# sar20-afbr-s50-adapter.net
KiCad netlist of a schematic drawn in Altium Designer
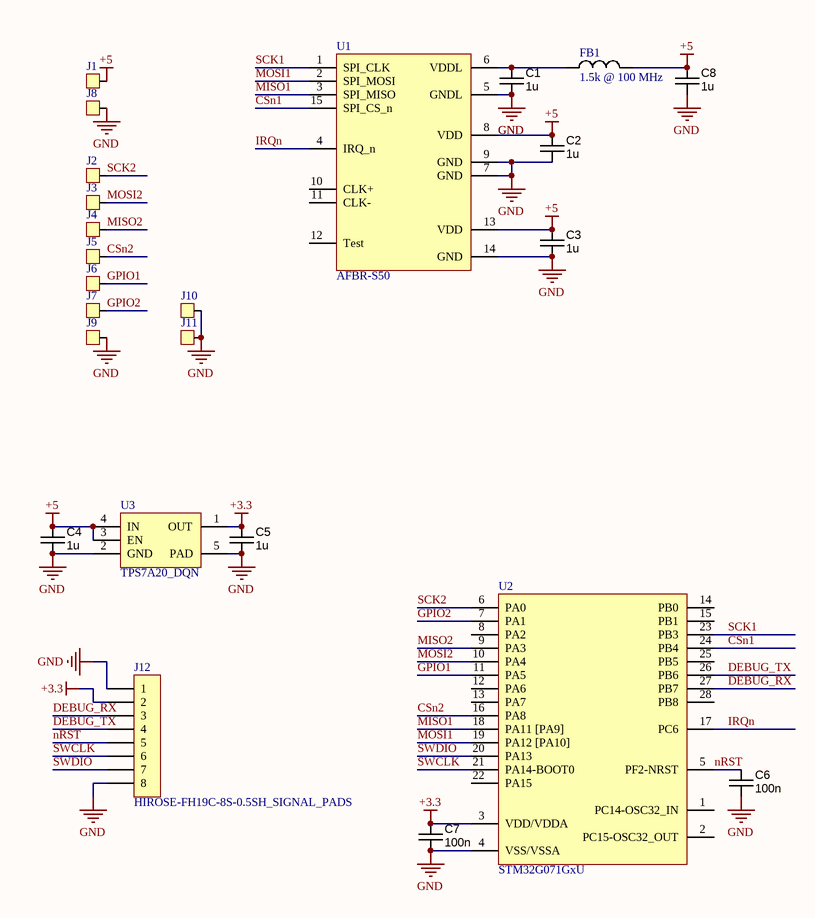
[diagram p0: sar20-afbr-s50-adapter.SchDoc]

(export (version "E")
  (design (tool "Eeschema 10.0.6"))
  (components
    (comp (ref "C1")
      (value "1u")
      (footprint "CAPC1005X55N")
      (description "Capacitor SMD Cer 100nF 10% 16V X5R 0402")
      (fields (field (name "TOLERANCE") "±10%"))
      (libsource (lib "PBL - Capacitors") (part "CAPC_100n_0402_X5R_16V_10%"))
    )
    (comp (ref "C2")
      (value "1u")
      (footprint "CAPC1005X55N")
      (description "Capacitor SMD Cer 100nF 10% 16V X5R 0402")
      (fields (field (name "TOLERANCE") "±10%"))
      (libsource (lib "PBL - Capacitors") (part "CAPC_100n_0402_X5R_16V_10%"))
    )
    (comp (ref "C3")
      (value "1u")
      (footprint "CAPC1005X55N")
      (description "Capacitor SMD Cer 100nF 10% 16V X5R 0402")
      (fields (field (name "TOLERANCE") "±10%"))
      (libsource (lib "PBL - Capacitors") (part "CAPC_100n_0402_X5R_16V_10%"))
    )
    (comp (ref "C4")
      (value "1u")
      (footprint "CAPC1005X55N")
      (description "Capacitor SMD Cer 100nF 10% 16V X5R 0402")
      (fields (field (name "TOLERANCE") "±10%"))
      (libsource (lib "PBL - Capacitors") (part "CAPC_100n_0402_X5R_16V_10%"))
    )
    (comp (ref "C5")
      (value "1u")
      (footprint "CAPC1005X55N")
      (description "Capacitor SMD Cer 100nF 10% 16V X5R 0402")
      (fields (field (name "TOLERANCE") "±10%"))
      (libsource (lib "PBL - Capacitors") (part "CAPC_100n_0402_X5R_16V_10%"))
    )
    (comp (ref "C6")
      (value "100n")
      (footprint "CAPC0603X04N")
      (fields (field (name "Comment") "CAPC_100n_0201"))
      (libsource (lib "passive") (part "CAPC_100n_0201"))
    )
    (comp (ref "C7")
      (value "100n")
      (footprint "CAPC0603X04N")
      (fields (field (name "Comment") "CAPC_100n_0201"))
      (libsource (lib "passive") (part "CAPC_100n_0201"))
    )
    (comp (ref "C8")
      (value "1u")
      (footprint "CAPC1005X55N")
      (description "Capacitor SMD Cer 100nF 10% 16V X5R 0402")
      (fields (field (name "TOLERANCE") "±10%"))
      (libsource (lib "PBL - Capacitors") (part "CAPC_100n_0402_X5R_16V_10%"))
    )
    (comp (ref "FB1")
      (value "1.5k @ 100 MHz")
      (footprint "RESC1005X40N")
      (libsource (lib "sar20-afbr-s50-adapter") (part "FERRITE_BEAD"))
    )
    (comp (ref "J1")
      (value "SOLDER-PAD")
      (footprint "PAD-0610")
      (libsource (lib "connectors") (part "SOLDER-PAD"))
    )
    (comp (ref "J2")
      (value "SOLDER-PAD")
      (footprint "PAD-0610")
      (libsource (lib "connectors") (part "SOLDER-PAD"))
    )
    (comp (ref "J3")
      (value "SOLDER-PAD")
      (footprint "PAD-0610")
      (libsource (lib "connectors") (part "SOLDER-PAD"))
    )
    (comp (ref "J4")
      (value "SOLDER-PAD")
      (footprint "PAD-0610")
      (libsource (lib "connectors") (part "SOLDER-PAD"))
    )
    (comp (ref "J5")
      (value "SOLDER-PAD")
      (footprint "PAD-0610")
      (libsource (lib "connectors") (part "SOLDER-PAD"))
    )
    (comp (ref "J6")
      (value "SOLDER-PAD")
      (footprint "PAD-0610")
      (libsource (lib "connectors") (part "SOLDER-PAD"))
    )
    (comp (ref "J7")
      (value "SOLDER-PAD")
      (footprint "PAD-0610")
      (libsource (lib "connectors") (part "SOLDER-PAD"))
    )
    (comp (ref "J8")
      (value "SOLDER-PAD")
      (footprint "PAD-0610")
      (libsource (lib "connectors") (part "SOLDER-PAD"))
    )
    (comp (ref "J9")
      (value "SOLDER-PAD")
      (footprint "PAD-0610")
      (libsource (lib "connectors") (part "SOLDER-PAD"))
    )
    (comp (ref "J10")
      (value "SOLDER-PAD")
      (footprint "PAD-0610")
      (libsource (lib "connectors") (part "SOLDER-PAD"))
    )
    (comp (ref "J11")
      (value "SOLDER-PAD")
      (footprint "PAD-0610")
      (libsource (lib "connectors") (part "SOLDER-PAD"))
    )
    (comp (ref "J12")
      (value "HIROSE-FH19C-8S-0.5SH_SIGNAL_PADS")
      (footprint "HIROSE-FH19C-8S-0.5SH_SIGNAL_PADS")
      (libsource (lib "sar20-afbr-s50-adapter") (part "HIROSE-FH19C-8S-0.5SH_SIGNAL_PADS"))
    )
    (comp (ref "U1")
      (value "AFBR-S50")
      (footprint "AFBR-S50")
      (libsource (lib "sar20-afbr-s50-adapter") (part "AFBR-S50"))
    )
    (comp (ref "U2")
      (value "STM32G071GxU")
      (footprint "QFN50P400X400X60-28N")
      (libsource (lib "sar20-afbr-s50-adapter") (part "STM32G071GxU"))
    )
    (comp (ref "U3")
      (value "TPS7A20_DQN")
      (footprint "TI_X2SON_DQN0004A")
      (libsource (lib "texas_instruments") (part "TPS7A20_DQN"))
    )
  )
  (nets
    (net (code "1") (name "+3.3") (class "Default")
      (node (ref "C5") (pin "2") (pintype "passive"))
      (node (ref "C7") (pin "2") (pinfunction "2_2") (pintype "passive"))
      (node (ref "J12") (pin "2") (pinfunction "2_2") (pintype "passive"))
      (node (ref "U2") (pin "3") (pinfunction "VDD/VDDA_3") (pintype "passive"))
      (node (ref "U3") (pin "1") (pinfunction "OUT_1") (pintype "passive"))
    )
    (net (code "2") (name "+5") (class "Default")
      (node (ref "C2") (pin "2") (pintype "passive"))
      (node (ref "C3") (pin "2") (pintype "passive"))
      (node (ref "C4") (pin "2") (pintype "passive"))
      (node (ref "C8") (pin "2") (pintype "passive"))
      (node (ref "FB1") (pin "2") (pinfunction "2_2") (pintype "passive"))
      (node (ref "J1") (pin "1") (pinfunction "1_1") (pintype "passive"))
      (node (ref "U1") (pin "13") (pinfunction "VDD_13") (pintype "passive"))
      (node (ref "U1") (pin "8") (pinfunction "VDD_8") (pintype "passive"))
      (node (ref "U3") (pin "3") (pinfunction "EN_3") (pintype "passive"))
      (node (ref "U3") (pin "4") (pinfunction "IN_4") (pintype "passive"))
    )
    (net (code "3") (name "/CSn1") (class "Default")
      (node (ref "U1") (pin "15") (pinfunction "SPI_CS_n_15") (pintype "passive"))
      (node (ref "U2") (pin "24") (pinfunction "PB4_24") (pintype "passive"))
    )
    (net (code "4") (name "/CSn2") (class "Default")
      (node (ref "J5") (pin "1") (pinfunction "1_1") (pintype "passive"))
      (node (ref "U2") (pin "16") (pinfunction "PA8_16") (pintype "passive"))
    )
    (net (code "5") (name "/DEBUG_RX") (class "Default")
      (node (ref "J12") (pin "3") (pinfunction "3_3") (pintype "passive"))
      (node (ref "U2") (pin "27") (pinfunction "PB7_27") (pintype "passive"))
    )
    (net (code "6") (name "/DEBUG_TX") (class "Default")
      (node (ref "J12") (pin "4") (pinfunction "4_4") (pintype "passive"))
      (node (ref "U2") (pin "26") (pinfunction "PB6_26") (pintype "passive"))
    )
    (net (code "7") (name "/GPIO1") (class "Default")
      (node (ref "J6") (pin "1") (pinfunction "1_1") (pintype "passive"))
      (node (ref "U2") (pin "11") (pinfunction "PA5_11") (pintype "passive"))
    )
    (net (code "8") (name "/GPIO2") (class "Default")
      (node (ref "J7") (pin "1") (pinfunction "1_1") (pintype "passive"))
      (node (ref "U2") (pin "7") (pinfunction "PA1_7") (pintype "passive"))
    )
    (net (code "9") (name "/IRQn") (class "Default")
      (node (ref "U1") (pin "4") (pinfunction "IRQ_n_4") (pintype "passive"))
      (node (ref "U2") (pin "17") (pinfunction "PC6_17") (pintype "passive"))
    )
    (net (code "10") (name "/MISO1") (class "Default")
      (node (ref "U1") (pin "3") (pinfunction "SPI_MISO_3") (pintype "passive"))
      (node (ref "U2") (pin "18") (pinfunction "PA11_[PA9]_18") (pintype "passive"))
    )
    (net (code "11") (name "/MISO2") (class "Default")
      (node (ref "J4") (pin "1") (pinfunction "1_1") (pintype "passive"))
      (node (ref "U2") (pin "9") (pinfunction "PA3_9") (pintype "passive"))
    )
    (net (code "12") (name "/MOSI1") (class "Default")
      (node (ref "U1") (pin "2") (pinfunction "SPI_MOSI_2") (pintype "passive"))
      (node (ref "U2") (pin "19") (pinfunction "PA12_[PA10]_19") (pintype "passive"))
    )
    (net (code "13") (name "/MOSI2") (class "Default")
      (node (ref "J3") (pin "1") (pinfunction "1_1") (pintype "passive"))
      (node (ref "U2") (pin "10") (pinfunction "PA4_10") (pintype "passive"))
    )
    (net (code "14") (name "/SCK1") (class "Default")
      (node (ref "U1") (pin "1") (pinfunction "SPI_CLK_1") (pintype "passive"))
      (node (ref "U2") (pin "23") (pinfunction "PB3_23") (pintype "passive"))
    )
    (net (code "15") (name "/SCK2") (class "Default")
      (node (ref "J2") (pin "1") (pinfunction "1_1") (pintype "passive"))
      (node (ref "U2") (pin "6") (pinfunction "PA0_6") (pintype "passive"))
    )
    (net (code "16") (name "/SWCLK") (class "Default")
      (node (ref "J12") (pin "6") (pinfunction "6_6") (pintype "passive"))
      (node (ref "U2") (pin "21") (pinfunction "PA14-BOOT0_21") (pintype "passive"))
    )
    (net (code "17") (name "/SWDIO") (class "Default")
      (node (ref "J12") (pin "7") (pinfunction "7_7") (pintype "passive"))
      (node (ref "U2") (pin "20") (pinfunction "PA13_20") (pintype "passive"))
    )
    (net (code "18") (name "/nRST") (class "Default")
      (node (ref "C6") (pin "2") (pinfunction "2_2") (pintype "passive"))
      (node (ref "J12") (pin "5") (pinfunction "5_5") (pintype "passive"))
      (node (ref "U2") (pin "5") (pinfunction "PF2-NRST_5") (pintype "passive"))
    )
    (net (code "19") (name "GND") (class "Default")
      (node (ref "C1") (pin "1") (pintype "passive"))
      (node (ref "C2") (pin "1") (pintype "passive"))
      (node (ref "C3") (pin "1") (pintype "passive"))
      (node (ref "C4") (pin "1") (pintype "passive"))
      (node (ref "C5") (pin "1") (pintype "passive"))
      (node (ref "C6") (pin "1") (pinfunction "1_1") (pintype "passive"))
      (node (ref "C7") (pin "1") (pinfunction "1_1") (pintype "passive"))
      (node (ref "C8") (pin "1") (pintype "passive"))
      (node (ref "J10") (pin "1") (pinfunction "1_1") (pintype "passive"))
      (node (ref "J11") (pin "1") (pinfunction "1_1") (pintype "passive"))
      (node (ref "J12") (pin "1") (pinfunction "1_1") (pintype "passive"))
      (node (ref "J12") (pin "8") (pinfunction "8_8") (pintype "passive"))
      (node (ref "J8") (pin "1") (pinfunction "1_1") (pintype "passive"))
      (node (ref "J9") (pin "1") (pinfunction "1_1") (pintype "passive"))
      (node (ref "U1") (pin "14") (pinfunction "GND_14") (pintype "passive"))
      (node (ref "U1") (pin "5") (pinfunction "GNDL_5") (pintype "passive"))
      (node (ref "U1") (pin "7") (pinfunction "GND_7") (pintype "passive"))
      (node (ref "U1") (pin "9") (pinfunction "GND_9") (pintype "passive"))
      (node (ref "U2") (pin "4") (pinfunction "VSS/VSSA_4") (pintype "passive"))
      (node (ref "U3") (pin "2") (pinfunction "GND_2") (pintype "passive"))
      (node (ref "U3") (pin "5") (pinfunction "PAD_5") (pintype "passive"))
    )
    (net (code "20") (name "Net-(U1-VDDL)") (class "Default")
      (node (ref "C1") (pin "2") (pintype "passive"))
      (node (ref "FB1") (pin "1") (pinfunction "1_1") (pintype "passive"))
      (node (ref "U1") (pin "6") (pinfunction "VDDL_6") (pintype "passive"))
    )
    (net (code "21") (name "unconnected-(U1-CLK+-Pad10)") (class "Default")
      (node (ref "U1") (pin "10") (pinfunction "CLK+_10") (pintype "passive"))
    )
    (net (code "22") (name "unconnected-(U1-CLK--Pad11)") (class "Default")
      (node (ref "U1") (pin "11") (pinfunction "CLK-_11") (pintype "passive"))
    )
    (net (code "23") (name "unconnected-(U1-Test-Pad12)") (class "Default")
      (node (ref "U1") (pin "12") (pinfunction "Test_12") (pintype "passive"))
    )
    (net (code "24") (name "unconnected-(U2-PA2-Pad8)") (class "Default")
      (node (ref "U2") (pin "8") (pinfunction "PA2_8") (pintype "passive"))
    )
    (net (code "25") (name "unconnected-(U2-PA6-Pad12)") (class "Default")
      (node (ref "U2") (pin "12") (pinfunction "PA6_12") (pintype "passive"))
    )
    (net (code "26") (name "unconnected-(U2-PA7-Pad13)") (class "Default")
      (node (ref "U2") (pin "13") (pinfunction "PA7_13") (pintype "passive"))
    )
    (net (code "27") (name "unconnected-(U2-PA15-Pad22)") (class "Default")
      (node (ref "U2") (pin "22") (pinfunction "PA15_22") (pintype "passive"))
    )
    (net (code "28") (name "unconnected-(U2-PB0-Pad14)") (class "Default")
      (node (ref "U2") (pin "14") (pinfunction "PB0_14") (pintype "passive"))
    )
    (net (code "29") (name "unconnected-(U2-PB1-Pad15)") (class "Default")
      (node (ref "U2") (pin "15") (pinfunction "PB1_15") (pintype "passive"))
    )
    (net (code "30") (name "unconnected-(U2-PB5-Pad25)") (class "Default")
      (node (ref "U2") (pin "25") (pinfunction "PB5_25") (pintype "passive"))
    )
    (net (code "31") (name "unconnected-(U2-PB8-Pad28)") (class "Default")
      (node (ref "U2") (pin "28") (pinfunction "PB8_28") (pintype "passive"))
    )
    (net (code "32") (name "unconnected-(U2-PC14-OSC32_IN-Pad1)") (class "Default")
      (node (ref "U2") (pin "1") (pinfunction "PC14-OSC32_IN_1") (pintype "passive"))
    )
    (net (code "33") (name "unconnected-(U2-PC15-OSC32_OUT-Pad2)") (class "Default")
      (node (ref "U2") (pin "2") (pinfunction "PC15-OSC32_OUT_2") (pintype "passive"))
    )
  )
)
